# Sheet1.net
KiCad netlist of a schematic drawn in Altium Designer
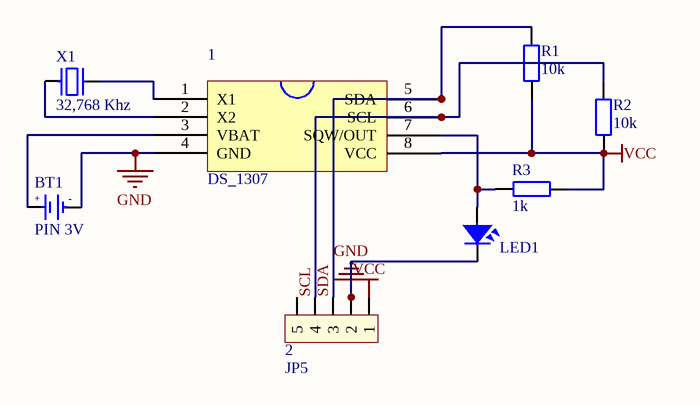
[diagram p0: Sheet1.SchDoc]

(export (version "E")
  (design (tool "Eeschema 10.0.6"))
  (components
    (comp (ref "1")
      (value "DS_1307")
      (footprint "DIP8_DS1307")
      (libsource (lib "syhaunguyen") (part "DS_1307"))
    )
    (comp (ref "2") (value "JP5") (footprint "JP5") (libsource (lib "syhaunguyen") (part "JP5")))
    (comp (ref "BT1")
      (value "PIN 3V")
      (footprint "PIN3V")
      (description "Battery 3VDC")
      (libsource (lib "syhaunguyen") (part "PIN 3V"))
    )
    (comp (ref "LED1")
      (value "LED")
      (footprint "LED-3")
      (description "LED Single colour Green and Red")
      (libsource (lib "syhaunguyen") (part "LED"))
    )
    (comp (ref "R1")
      (value "10k")
      (footprint "R1/2W")
      (description "Resistor 1/4W")
      (libsource (lib "syhaunguyen") (part "R1/4W"))
    )
    (comp (ref "R2")
      (value "10k")
      (footprint "R1/2W")
      (description "Resistor 1/4W")
      (libsource (lib "syhaunguyen") (part "R1/4W"))
    )
    (comp (ref "R3")
      (value "1k")
      (footprint "R1/4W")
      (description "Resistor 1/4W")
      (libsource (lib "syhaunguyen") (part "R1/4W"))
    )
    (comp (ref "X1")
      (value "32,768 Khz")
      (footprint "XT32k")
      (description "Crystal 32,768kHz for timer real")
      (libsource (lib "syhaunguyen") (part "XT32k"))
    )
  )
  (nets
    (net (code "1") (name "/SCL") (class "Default")
      (node (ref "1") (pin "6") (pinfunction "SCL_6") (pintype "passive"))
      (node (ref "2") (pin "4") (pinfunction "4_4") (pintype "passive"))
      (node (ref "R2") (pin "2") (pinfunction "2_2") (pintype "passive"))
    )
    (net (code "2") (name "/SDA") (class "Default")
      (node (ref "1") (pin "5") (pinfunction "SDA_5") (pintype "passive"))
      (node (ref "2") (pin "3") (pinfunction "3_3") (pintype "passive"))
      (node (ref "R1") (pin "2") (pinfunction "2_2") (pintype "passive"))
    )
    (net (code "3") (name "GND") (class "Default")
      (node (ref "1") (pin "4") (pinfunction "GND_4") (pintype "passive"))
      (node (ref "2") (pin "2") (pinfunction "2_2") (pintype "passive"))
      (node (ref "BT1") (pin "2") (pinfunction "GND_2") (pintype "passive"))
      (node (ref "LED1") (pin "2") (pinfunction "2_2") (pintype "passive"))
    )
    (net (code "4") (name "Net-(1-SQW{slash}OUT)") (class "Default")
      (node (ref "1") (pin "7") (pinfunction "SQW/OUT_7") (pintype "passive"))
      (node (ref "LED1") (pin "1") (pinfunction "1_1") (pintype "passive"))
      (node (ref "R3") (pin "1") (pinfunction "1_1") (pintype "passive"))
    )
    (net (code "5") (name "Net-(1-VBAT)") (class "Default")
      (node (ref "1") (pin "3") (pinfunction "VBAT_3") (pintype "passive"))
      (node (ref "BT1") (pin "1") (pinfunction "+3V_1") (pintype "passive"))
    )
    (net (code "6") (name "Net-(1-X1)") (class "Default")
      (node (ref "1") (pin "1") (pinfunction "X1_1") (pintype "passive"))
      (node (ref "X1") (pin "2") (pinfunction "2_2") (pintype "passive"))
    )
    (net (code "7") (name "Net-(1-X2)") (class "Default")
      (node (ref "1") (pin "2") (pinfunction "X2_2") (pintype "passive"))
      (node (ref "X1") (pin "1") (pinfunction "1_1") (pintype "passive"))
    )
    (net (code "8") (name "VCC") (class "Default")
      (node (ref "1") (pin "8") (pinfunction "VCC_8") (pintype "passive"))
      (node (ref "2") (pin "1") (pinfunction "1_1") (pintype "passive"))
      (node (ref "R1") (pin "1") (pinfunction "1_1") (pintype "passive"))
      (node (ref "R2") (pin "1") (pinfunction "1_1") (pintype "passive"))
      (node (ref "R3") (pin "2") (pinfunction "2_2") (pintype "passive"))
    )
    (net (code "9") (name "unconnected-(2-Pad5)") (class "Default")
      (node (ref "2") (pin "5") (pinfunction "5_5") (pintype "passive"))
    )
  )
)
